# REGULACION.net
KiCad netlist of a schematic drawn in Altium Designer
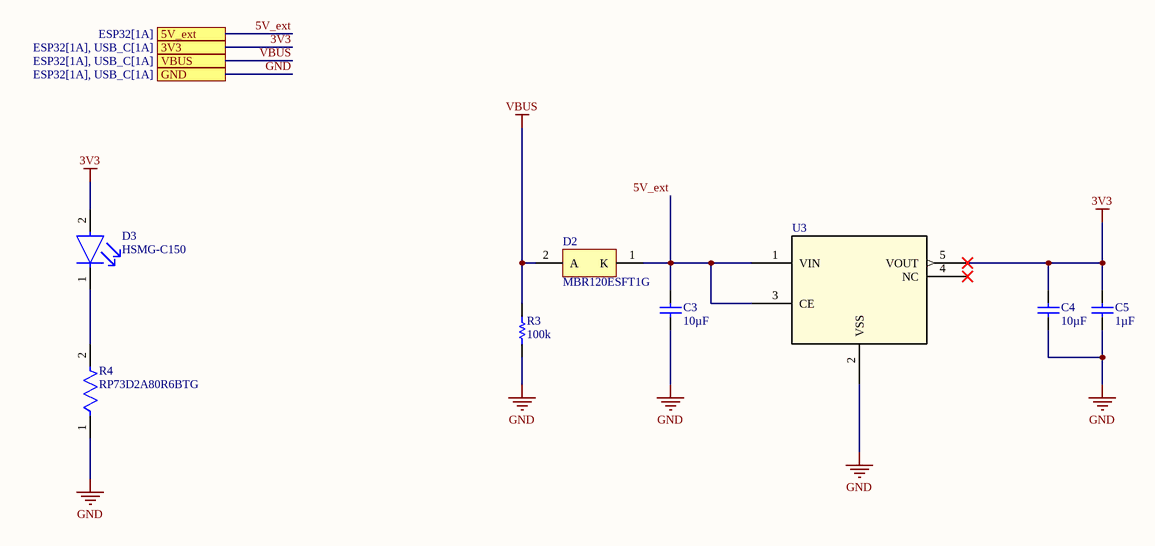
[diagram p0: REGULACION.SchDoc]

(export (version "E")
  (design (tool "Eeschema 10.0.6"))
  (components
    (comp (ref "C3")
      (value "10µF")
      (footprint "CAPC2013X140X50ML20T25")
      (description "10µF ±10% 16V Ceramic Capacitor X5R 0805 (2012 Metric)")
      (fields (field (name "PART NUMBER") "CL21A106KOQNNNG"))
      (libsource (lib "Altium Content Vault") (part "CAP"))
    )
    (comp (ref "C4")
      (value "10µF")
      (footprint "CAPC2013X140X50ML20T25")
      (description "10µF ±10% 16V Ceramic Capacitor X5R 0805 (2012 Metric)")
      (fields (field (name "PART NUMBER") "CL21A106KOQNNNG"))
      (libsource (lib "Altium Content Vault") (part "CAP"))
    )
    (comp (ref "C5")
      (value "1µF")
      (footprint "CAPC2013X145X50ML20T25")
      (description "1µF ±10% 16V Ceramic Capacitor X7R 0805 (2012 Metric)")
      (fields (field (name "MANUFACTURER") "Kemet") (field (name "PART NUMBER") "C0805C105K4RAC7800"))
      (libsource (lib "Altium Content Vault") (part "CAP"))
    )
    (comp (ref "D2")
      (value "MBR120ESFT1G")
      (footprint "ONSC-SOD-123FL-2-498_V")
      (description "Schottky Power Rectifier, 2-Pin SOD-123, Pb-Free, Tape and Reel")
      (fields (field (name "MANUFACTURER") "On Semiconductor"))
      (libsource (lib "Altium Content Vault") (part "ONSC-D-K1A2-2_A"))
    )
    (comp (ref "D3")
      (value "HSMG-C150")
      (footprint "FP-HSMG-C150-MFG")
      (description "LED GREEN DIFFUSED 1206 SMD")
      (fields
        (field (name "MANUFACTURER") "Broadcom")
        (field (name "OCTOPART") "https://octopart.com/hsmg-c150-broadcom-71131304")
      )
      (libsource (lib "Altium Content Vault") (part "8706943c75ba83719d021d2fdc84c58"))
    )
    (comp (ref "R3")
      (value "100k")
      (footprint "RESC2013X60X40ML20T25")
      (description "100 kOhms ±0.1% 0.125W, 1/8W Chip Resistor 0805 (2012 Metric) Automotive AEC-Q200 Thin Film")
      (fields (field (name "PART NUMBER") "ERA6AEB104V") (field (name "MANUFACTURER") "Panasonic"))
      (libsource (lib "Altium Content Vault") (part "RES"))
    )
    (comp (ref "R4")
      (value "RP73D2A80R6BTG")
      (footprint "FP-RP732A-MFG")
      (description "RESISTOR, 0805 80.6Ω, 0.1% 15ppm/°C")
      (fields
        (field (name "OCTOPART") "https://octopart.com/rp73d2a80r6btg-te+connectivity-42011633")
        (field (name "MANUFACTURER") "TE Connectivity")
      )
      (libsource (lib "Altium Content Vault") (part "1029c3af85768c4190bb7ad29bc67b5"))
    )
    (comp (ref "U3")
      (value "~")
      (footprint "SOT-25_TOR-M")
      (description "No Description Available")
      (fields
        (field (name "MANUFACTURER_PART_NUMBER") "XC6210B332MR-G")
        (field (name "COPYRIGHT") "Copyright (C) 2022 Ultra Librarian. All rights reserved.")
      )
      (libsource (lib "Isidro_Library") (part "XC6210B332MR-G"))
    )
  )
  (nets
    (net (code "1") (name "/5V_ext") (class "Default")
      (node (ref "C3") (pin "2") (pinfunction "2_2") (pintype "passive"))
      (node (ref "D2") (pin "1") (pinfunction "K_1") (pintype "passive"))
      (node (ref "U3") (pin "1") (pinfunction "VIN_1") (pintype "power_in"))
      (node (ref "U3") (pin "3") (pinfunction "CE_3") (pintype "passive"))
    )
    (net (code "2") (name "3V3") (class "Default")
      (node (ref "C4") (pin "2") (pinfunction "2_2") (pintype "passive"))
      (node (ref "C5") (pin "2") (pinfunction "2_2") (pintype "passive"))
      (node (ref "D3") (pin "2") (pinfunction "A_2") (pintype "passive"))
      (node (ref "U3") (pin "5") (pinfunction "VOUT_5") (pintype "output"))
    )
    (net (code "3") (name "GND") (class "Default")
      (node (ref "C3") (pin "1") (pinfunction "1_1") (pintype "passive"))
      (node (ref "C4") (pin "1") (pinfunction "1_1") (pintype "passive"))
      (node (ref "C5") (pin "1") (pinfunction "1_1") (pintype "passive"))
      (node (ref "R3") (pin "1") (pinfunction "1_1") (pintype "passive"))
      (node (ref "R4") (pin "1") (pinfunction "1_1") (pintype "passive"))
      (node (ref "U3") (pin "2") (pinfunction "VSS_2") (pintype "passive"))
    )
    (net (code "4") (name "Net-(D3-C)") (class "Default")
      (node (ref "D3") (pin "1") (pinfunction "C_1") (pintype "passive"))
      (node (ref "R4") (pin "2") (pinfunction "2_2") (pintype "passive"))
    )
    (net (code "5") (name "VBUS") (class "Default")
      (node (ref "D2") (pin "2") (pinfunction "A_2") (pintype "passive"))
      (node (ref "R3") (pin "2") (pinfunction "2_2") (pintype "passive"))
    )
    (net (code "6") (name "unconnected-(U3-NC-Pad4)") (class "Default")
      (node (ref "U3") (pin "4") (pinfunction "NC_4") (pintype "passive+no_connect"))
    )
  )
)
